# microNrf.net
KiCad netlist of a schematic drawn in EAGLE
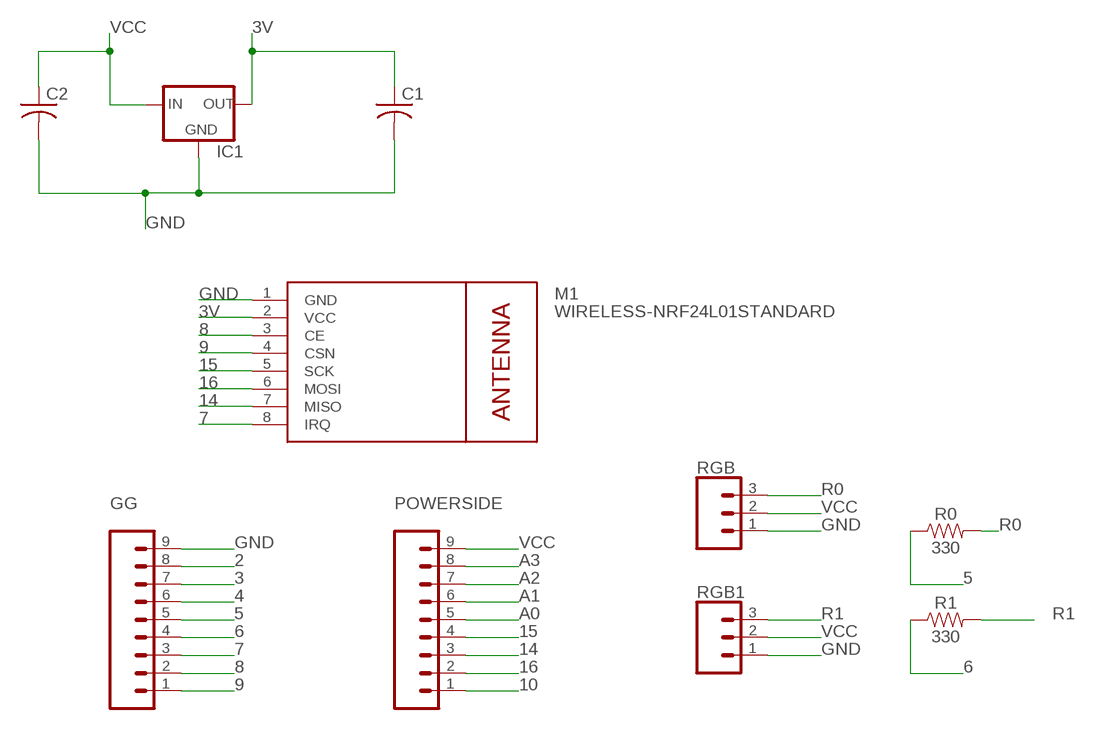
[diagram p0: schematic, sheet 1]

(export (version "E")
  (design (tool "Eeschema 10.0.6"))
  (components
    (comp (ref "C1")
      (value "C-US025-030X050")
      (footprint "eagle-import:C025-030X050")
      (libsource (lib "eagle-import") (part "C-US025-030X050"))
    )
    (comp (ref "C2")
      (value "C-US025-030X050")
      (footprint "eagle-import:C025-030X050")
      (libsource (lib "eagle-import") (part "C-US025-030X050"))
    )
    (comp (ref "GG")
      (value "CONN_09")
      (footprint "eagle-import:1X09")
      (libsource (lib "eagle-import") (part "CONN_09"))
    )
    (comp (ref "IC1")
      (value "MCP1700TRI")
      (footprint "eagle-import:TO92")
      (libsource (lib "eagle-import") (part "MCP1700TRI"))
    )
    (comp (ref "M1")
      (value "WIRELESS-NRF24L01STANDARD")
      (footprint "eagle-import:WIRELESS-NRF24L01")
      (libsource (lib "eagle-import") (part "WIRELESS-NRF24L01STANDARD"))
    )
    (comp (ref "POWERSIDE")
      (value "CONN_09")
      (footprint "eagle-import:1X09")
      (libsource (lib "eagle-import") (part "CONN_09"))
    )
    (comp (ref "R0")
      (value "330")
      (footprint "eagle-import:0603")
      (libsource (lib "eagle-import") (part "330OHM-0603-1/10W-1%"))
    )
    (comp (ref "R1")
      (value "330")
      (footprint "eagle-import:0603")
      (libsource (lib "eagle-import") (part "330OHM-0603-1/10W-1%"))
    )
    (comp (ref "RGB")
      (value "CONN_03LONGPADS")
      (footprint "eagle-import:1X03_LONGPADS")
      (libsource (lib "eagle-import") (part "CONN_03LONGPADS"))
    )
    (comp (ref "RGB1")
      (value "CONN_03LONGPADS")
      (footprint "eagle-import:1X03_LONGPADS")
      (libsource (lib "eagle-import") (part "CONN_03LONGPADS"))
    )
  )
  (nets
    (net (code "1") (name "/2") (class "Default")
      (node (ref "GG") (pin "8") (pinfunction "8_8") (pintype "passive"))
    )
    (net (code "2") (name "/3") (class "Default")
      (node (ref "GG") (pin "7") (pinfunction "7_7") (pintype "passive"))
    )
    (net (code "3") (name "/3V") (class "Default")
      (node (ref "C1") (pin "1") (pinfunction "1_1") (pintype "passive"))
      (node (ref "IC1") (pin "3") (pinfunction "OUT_3") (pintype "passive"))
      (node (ref "M1") (pin "2") (pinfunction "VCC_2") (pintype "power_in"))
    )
    (net (code "4") (name "/4") (class "Default")
      (node (ref "GG") (pin "6") (pinfunction "6_6") (pintype "passive"))
    )
    (net (code "5") (name "/5") (class "Default")
      (node (ref "GG") (pin "5") (pinfunction "5_5") (pintype "passive"))
      (node (ref "R0") (pin "1") (pinfunction "1_1") (pintype "passive"))
    )
    (net (code "6") (name "/6") (class "Default")
      (node (ref "GG") (pin "4") (pinfunction "4_4") (pintype "passive"))
      (node (ref "R1") (pin "1") (pinfunction "1_1") (pintype "passive"))
    )
    (net (code "7") (name "/7") (class "Default")
      (node (ref "GG") (pin "3") (pinfunction "3_3") (pintype "passive"))
      (node (ref "M1") (pin "8") (pinfunction "IRQ_8") (pintype "bidirectional"))
    )
    (net (code "8") (name "/8") (class "Default")
      (node (ref "GG") (pin "2") (pinfunction "2_2") (pintype "passive"))
      (node (ref "M1") (pin "3") (pinfunction "CE_3") (pintype "bidirectional"))
    )
    (net (code "9") (name "/9") (class "Default")
      (node (ref "GG") (pin "1") (pinfunction "1_1") (pintype "passive"))
      (node (ref "M1") (pin "4") (pinfunction "CSN_4") (pintype "bidirectional"))
    )
    (net (code "10") (name "/10") (class "Default")
      (node (ref "POWERSIDE") (pin "1") (pinfunction "1_1") (pintype "passive"))
    )
    (net (code "11") (name "/14") (class "Default")
      (node (ref "M1") (pin "7") (pinfunction "MISO_7") (pintype "bidirectional"))
      (node (ref "POWERSIDE") (pin "3") (pinfunction "3_3") (pintype "passive"))
    )
    (net (code "12") (name "/15") (class "Default")
      (node (ref "M1") (pin "5") (pinfunction "SCK_5") (pintype "bidirectional"))
      (node (ref "POWERSIDE") (pin "4") (pinfunction "4_4") (pintype "passive"))
    )
    (net (code "13") (name "/16") (class "Default")
      (node (ref "M1") (pin "6") (pinfunction "MOSI_6") (pintype "bidirectional"))
      (node (ref "POWERSIDE") (pin "2") (pinfunction "2_2") (pintype "passive"))
    )
    (net (code "14") (name "/A0") (class "Default")
      (node (ref "POWERSIDE") (pin "5") (pinfunction "5_5") (pintype "passive"))
    )
    (net (code "15") (name "/A1") (class "Default")
      (node (ref "POWERSIDE") (pin "6") (pinfunction "6_6") (pintype "passive"))
    )
    (net (code "16") (name "/A2") (class "Default")
      (node (ref "POWERSIDE") (pin "7") (pinfunction "7_7") (pintype "passive"))
    )
    (net (code "17") (name "/A3") (class "Default")
      (node (ref "POWERSIDE") (pin "8") (pinfunction "8_8") (pintype "passive"))
    )
    (net (code "18") (name "/GND") (class "Default")
      (node (ref "C1") (pin "2") (pinfunction "2_2") (pintype "passive"))
      (node (ref "C2") (pin "2") (pinfunction "2_2") (pintype "passive"))
      (node (ref "GG") (pin "9") (pinfunction "9_9") (pintype "passive"))
      (node (ref "IC1") (pin "1") (pinfunction "GND_1") (pintype "input"))
      (node (ref "M1") (pin "1") (pinfunction "GND_1") (pintype "power_in"))
      (node (ref "RGB") (pin "1") (pinfunction "1_1") (pintype "passive"))
      (node (ref "RGB1") (pin "1") (pinfunction "1_1") (pintype "passive"))
    )
    (net (code "19") (name "/R0") (class "Default")
      (node (ref "R0") (pin "2") (pinfunction "2_2") (pintype "passive"))
      (node (ref "RGB") (pin "3") (pinfunction "3_3") (pintype "passive"))
    )
    (net (code "20") (name "/R1") (class "Default")
      (node (ref "R1") (pin "2") (pinfunction "2_2") (pintype "passive"))
      (node (ref "RGB1") (pin "3") (pinfunction "3_3") (pintype "passive"))
    )
    (net (code "21") (name "/VCC") (class "Default")
      (node (ref "C2") (pin "1") (pinfunction "1_1") (pintype "passive"))
      (node (ref "IC1") (pin "2") (pinfunction "IN_2") (pintype "input"))
      (node (ref "POWERSIDE") (pin "9") (pinfunction "9_9") (pintype "passive"))
      (node (ref "RGB") (pin "2") (pinfunction "2_2") (pintype "passive"))
      (node (ref "RGB1") (pin "2") (pinfunction "2_2") (pintype "passive"))
    )
  )
)
